# Emitters.net
KiCad netlist of a schematic drawn in EAGLE
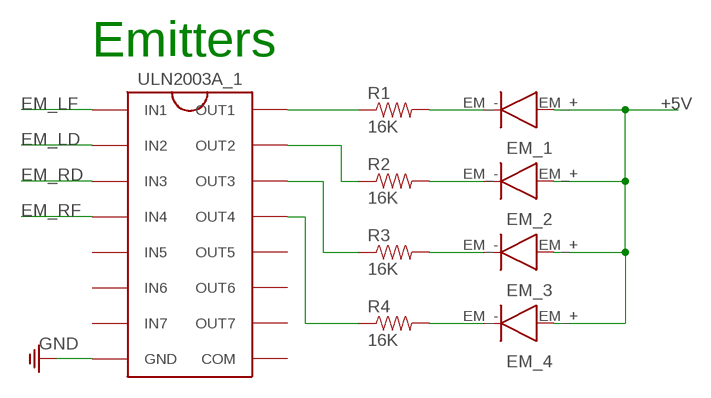
[diagram p0: schematic, sheet 1]

(export (version "E")
  (design (tool "Eeschema 10.0.6"))
  (components
    (comp (ref "EM_1")
      (value "SFH4545")
      (footprint "eagle-import:EMITTER")
      (libsource (lib "eagle-import") (part "SFH4545"))
    )
    (comp (ref "EM_2")
      (value "SFH4545")
      (footprint "eagle-import:EMITTER")
      (libsource (lib "eagle-import") (part "SFH4545"))
    )
    (comp (ref "EM_3")
      (value "SFH4545")
      (footprint "eagle-import:EMITTER")
      (libsource (lib "eagle-import") (part "SFH4545"))
    )
    (comp (ref "EM_4")
      (value "SFH4545")
      (footprint "eagle-import:EMITTER")
      (libsource (lib "eagle-import") (part "SFH4545"))
    )
    (comp (ref "R1")
      (value "16K")
      (footprint "eagle-import:0805")
      (libsource (lib "eagle-import") (part "RESISTOR_0805IN_2012MM"))
    )
    (comp (ref "R2")
      (value "16K")
      (footprint "eagle-import:0805")
      (libsource (lib "eagle-import") (part "RESISTOR_0805IN_2012MM"))
    )
    (comp (ref "R3")
      (value "16K")
      (footprint "eagle-import:0805")
      (libsource (lib "eagle-import") (part "RESISTOR_0805IN_2012MM"))
    )
    (comp (ref "R4")
      (value "16K")
      (footprint "eagle-import:0805")
      (libsource (lib "eagle-import") (part "RESISTOR_0805IN_2012MM"))
    )
    (comp (ref "ULN2003A_1")
      (value "ULN2003A")
      (footprint "eagle-import:ULN2003A")
      (libsource (lib "eagle-import") (part "ULN2003A"))
    )
  )
  (nets
    (net (code "1") (name "/+5V") (class "Default")
      (node (ref "EM_1") (pin "EM_+") (pinfunction "+_EM_+") (pintype "bidirectional"))
      (node (ref "EM_2") (pin "EM_+") (pinfunction "+_EM_+") (pintype "bidirectional"))
      (node (ref "EM_3") (pin "EM_+") (pinfunction "+_EM_+") (pintype "bidirectional"))
      (node (ref "EM_4") (pin "EM_+") (pinfunction "+_EM_+") (pintype "bidirectional"))
    )
    (net (code "2") (name "/EM_LD") (class "Default")
      (node (ref "ULN2003A_1") (pin "2B") (pinfunction "IN2_2B") (pintype "bidirectional"))
    )
    (net (code "3") (name "/EM_LF") (class "Default")
      (node (ref "ULN2003A_1") (pin "1B") (pinfunction "IN1_1B") (pintype "bidirectional"))
    )
    (net (code "4") (name "/EM_RD") (class "Default")
      (node (ref "ULN2003A_1") (pin "3B") (pinfunction "IN3_3B") (pintype "bidirectional"))
    )
    (net (code "5") (name "/EM_RF") (class "Default")
      (node (ref "ULN2003A_1") (pin "4B") (pinfunction "IN4_4B") (pintype "bidirectional"))
    )
    (net (code "6") (name "GND") (class "Default")
      (node (ref "ULN2003A_1") (pin "GND") (pinfunction "GND_GND") (pintype "power_in"))
    )
    (net (code "7") (name "Net-(EM_1--)") (class "Default")
      (node (ref "EM_1") (pin "EM_-") (pinfunction "-_EM_-") (pintype "bidirectional"))
      (node (ref "R1") (pin "2") (pinfunction "2_2") (pintype "passive"))
    )
    (net (code "8") (name "Net-(EM_2--)") (class "Default")
      (node (ref "EM_2") (pin "EM_-") (pinfunction "-_EM_-") (pintype "bidirectional"))
      (node (ref "R2") (pin "2") (pinfunction "2_2") (pintype "passive"))
    )
    (net (code "9") (name "Net-(EM_3--)") (class "Default")
      (node (ref "EM_3") (pin "EM_-") (pinfunction "-_EM_-") (pintype "bidirectional"))
      (node (ref "R3") (pin "2") (pinfunction "2_2") (pintype "passive"))
    )
    (net (code "10") (name "Net-(EM_4--)") (class "Default")
      (node (ref "EM_4") (pin "EM_-") (pinfunction "-_EM_-") (pintype "bidirectional"))
      (node (ref "R4") (pin "2") (pinfunction "2_2") (pintype "passive"))
    )
    (net (code "11") (name "Net-(ULN2003A_1-OUT1)") (class "Default")
      (node (ref "R1") (pin "1") (pinfunction "1_1") (pintype "passive"))
      (node (ref "ULN2003A_1") (pin "1C") (pinfunction "OUT1_1C") (pintype "bidirectional"))
    )
    (net (code "12") (name "Net-(ULN2003A_1-OUT2)") (class "Default")
      (node (ref "R2") (pin "1") (pinfunction "1_1") (pintype "passive"))
      (node (ref "ULN2003A_1") (pin "2C") (pinfunction "OUT2_2C") (pintype "bidirectional"))
    )
    (net (code "13") (name "Net-(ULN2003A_1-OUT3)") (class "Default")
      (node (ref "R3") (pin "1") (pinfunction "1_1") (pintype "passive"))
      (node (ref "ULN2003A_1") (pin "3C") (pinfunction "OUT3_3C") (pintype "bidirectional"))
    )
    (net (code "14") (name "Net-(ULN2003A_1-OUT4)") (class "Default")
      (node (ref "R4") (pin "1") (pinfunction "1_1") (pintype "passive"))
      (node (ref "ULN2003A_1") (pin "4C") (pinfunction "OUT4_4C") (pintype "bidirectional"))
    )
    (net (code "15") (name "unconnected-(ULN2003A_1-IN5-Pad5B)") (class "Default")
      (node (ref "ULN2003A_1") (pin "5B") (pinfunction "IN5_5B") (pintype "bidirectional"))
    )
    (net (code "16") (name "unconnected-(ULN2003A_1-IN6-Pad6B)") (class "Default")
      (node (ref "ULN2003A_1") (pin "6B") (pinfunction "IN6_6B") (pintype "bidirectional"))
    )
    (net (code "17") (name "unconnected-(ULN2003A_1-IN7-Pad7B)") (class "Default")
      (node (ref "ULN2003A_1") (pin "7B") (pinfunction "IN7_7B") (pintype "bidirectional"))
    )
    (net (code "18") (name "unconnected-(ULN2003A_1-OUT5-Pad5C)") (class "Default")
      (node (ref "ULN2003A_1") (pin "5C") (pinfunction "OUT5_5C") (pintype "bidirectional"))
    )
    (net (code "19") (name "unconnected-(ULN2003A_1-OUT6-Pad6C)") (class "Default")
      (node (ref "ULN2003A_1") (pin "6C") (pinfunction "OUT6_6C") (pintype "bidirectional"))
    )
    (net (code "20") (name "unconnected-(ULN2003A_1-OUT7-Pad7C)") (class "Default")
      (node (ref "ULN2003A_1") (pin "7C") (pinfunction "OUT7_7C") (pintype "bidirectional"))
    )
    (net (code "21") (name "unconnected-(ULN2003A_1-PadCOM)") (class "Default")
      (node (ref "ULN2003A_1") (pin "COM") (pinfunction "COM_COM") (pintype "bidirectional"))
    )
  )
)
